# Sonar_Power_Schematic_LT1962.net
KiCad netlist of a schematic drawn in EAGLE
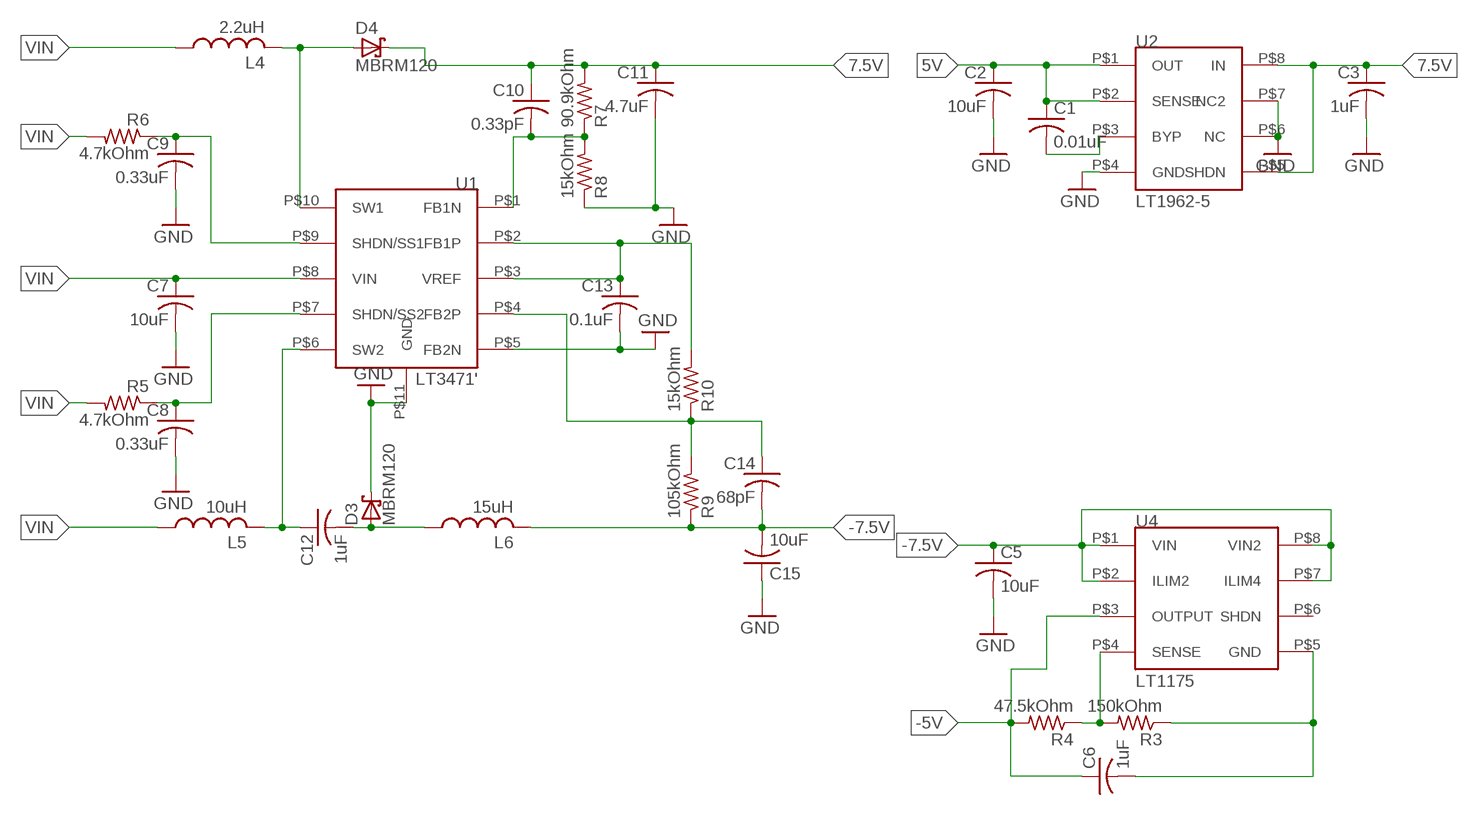
[diagram p0: schematic, sheet 1]

(export (version "E")
  (design (tool "Eeschema 10.0.6"))
  (components
    (comp (ref "C1")
      (value "0.01uF")
      (footprint "eagle-import:C0603")
      (libsource (lib "eagle-import") (part "C-USC0603"))
    )
    (comp (ref "C2")
      (value "10uF")
      (footprint "eagle-import:C0603")
      (libsource (lib "eagle-import") (part "C-USC0603"))
    )
    (comp (ref "C3")
      (value "1uF")
      (footprint "eagle-import:C0603")
      (libsource (lib "eagle-import") (part "C-USC0603"))
    )
    (comp (ref "C5")
      (value "10uF")
      (footprint "eagle-import:C0603")
      (libsource (lib "eagle-import") (part "C-USC0603"))
    )
    (comp (ref "C6")
      (value "1uF")
      (footprint "eagle-import:C0603")
      (libsource (lib "eagle-import") (part "C-USC0603"))
    )
    (comp (ref "C7")
      (value "10uF")
      (footprint "eagle-import:C0603")
      (libsource (lib "eagle-import") (part "C-USC0603"))
    )
    (comp (ref "C8")
      (value "0.33uF")
      (footprint "eagle-import:C0603")
      (libsource (lib "eagle-import") (part "C-USC0603"))
    )
    (comp (ref "C9")
      (value "0.33uF")
      (footprint "eagle-import:C0603")
      (libsource (lib "eagle-import") (part "C-USC0603"))
    )
    (comp (ref "C10")
      (value "0.33pF")
      (footprint "eagle-import:C0603")
      (libsource (lib "eagle-import") (part "C-USC0603"))
    )
    (comp (ref "C11")
      (value "4.7uF")
      (footprint "eagle-import:C0603")
      (libsource (lib "eagle-import") (part "C-USC0603"))
    )
    (comp (ref "C12")
      (value "1uF")
      (footprint "eagle-import:C0603")
      (libsource (lib "eagle-import") (part "C-USC0603"))
    )
    (comp (ref "C13")
      (value "0.1uF")
      (footprint "eagle-import:C0603")
      (libsource (lib "eagle-import") (part "C-USC0603"))
    )
    (comp (ref "C14")
      (value "68pF")
      (footprint "eagle-import:C0603")
      (libsource (lib "eagle-import") (part "C-USC0603"))
    )
    (comp (ref "C15")
      (value "10uF")
      (footprint "eagle-import:C0603")
      (libsource (lib "eagle-import") (part "C-USC0603"))
    )
    (comp (ref "D3")
      (value "MBRM120")
      (footprint "eagle-import:DO-216AA")
      (libsource (lib "eagle-import") (part "MBRM120"))
    )
    (comp (ref "D4")
      (value "MBRM120")
      (footprint "eagle-import:DO-216AA")
      (libsource (lib "eagle-import") (part "MBRM120"))
    )
    (comp (ref "L4")
      (value "2.2uH")
      (footprint "eagle-import:NS4.9X4.9")
      (libsource (lib "eagle-import") (part "LQH5BPN2R2N38L"))
    )
    (comp (ref "L5")
      (value "10uH")
      (footprint "eagle-import:NS5X5")
      (libsource (lib "eagle-import") (part "VLS5045EX-100M2"))
    )
    (comp (ref "L6")
      (value "15uH")
      (footprint "eagle-import:NS5X5")
      (libsource (lib "eagle-import") (part "VLS5045EX-150M-CA1"))
    )
    (comp (ref "R3")
      (value "150kOhm")
      (footprint "eagle-import:R0603")
      (libsource (lib "eagle-import") (part "R-US_R0603"))
    )
    (comp (ref "R4")
      (value "47.5kOhm")
      (footprint "eagle-import:R0603")
      (libsource (lib "eagle-import") (part "R-US_R0603"))
    )
    (comp (ref "R5")
      (value "4.7kOhm")
      (footprint "eagle-import:R0603")
      (libsource (lib "eagle-import") (part "R-US_R0603"))
    )
    (comp (ref "R6")
      (value "4.7kOhm")
      (footprint "eagle-import:R0603")
      (libsource (lib "eagle-import") (part "R-US_R0603"))
    )
    (comp (ref "R7")
      (value "90.9kOhm")
      (footprint "eagle-import:R0603")
      (libsource (lib "eagle-import") (part "R-US_R0603"))
    )
    (comp (ref "R8")
      (value "15kOhm")
      (footprint "eagle-import:R0603")
      (libsource (lib "eagle-import") (part "R-US_R0603"))
    )
    (comp (ref "R9")
      (value "105kOhm")
      (footprint "eagle-import:R0603")
      (libsource (lib "eagle-import") (part "R-US_R0603"))
    )
    (comp (ref "R10")
      (value "15kOhm")
      (footprint "eagle-import:R0603")
      (libsource (lib "eagle-import") (part "R-US_R0603"))
    )
    (comp (ref "U1")
      (value "LT3471'")
      (footprint "eagle-import:10-WFDFN")
      (libsource (lib "eagle-import") (part "LT3471'"))
    )
    (comp (ref "U2")
      (value "LT1962-5")
      (footprint "eagle-import:8-MSOP")
      (libsource (lib "eagle-import") (part "LT1962-5"))
    )
    (comp (ref "U4")
      (value "LT1175")
      (footprint "eagle-import:8-SOIC")
      (libsource (lib "eagle-import") (part "LT1175"))
    )
  )
  (nets
    (net (code "1") (name "-5V") (class "Default")
      (node (ref "C6") (pin "1") (pinfunction "1_1") (pintype "passive"))
      (node (ref "R4") (pin "2") (pinfunction "2_2") (pintype "passive"))
      (node (ref "U4") (pin "P$3") (pinfunction "OUTPUT_P$3") (pintype "bidirectional"))
    )
    (net (code "2") (name "-7.5V") (class "Default")
      (node (ref "C14") (pin "2") (pinfunction "2_2") (pintype "passive"))
      (node (ref "C15") (pin "2") (pinfunction "2_2") (pintype "passive"))
      (node (ref "C5") (pin "1") (pinfunction "1_1") (pintype "passive"))
      (node (ref "L6") (pin "P$2") (pinfunction "2_P$2") (pintype "passive"))
      (node (ref "R9") (pin "1") (pinfunction "1_1") (pintype "passive"))
      (node (ref "U4") (pin "P$1") (pinfunction "VIN_P$1") (pintype "power_in"))
      (node (ref "U4") (pin "P$2") (pinfunction "ILIM2_P$2") (pintype "bidirectional"))
      (node (ref "U4") (pin "P$7") (pinfunction "ILIM4_P$7") (pintype "bidirectional"))
      (node (ref "U4") (pin "P$8") (pinfunction "VIN2_P$8") (pintype "power_in"))
    )
    (net (code "3") (name "5V") (class "Default")
      (node (ref "C1") (pin "1") (pinfunction "1_1") (pintype "passive"))
      (node (ref "C2") (pin "1") (pinfunction "1_1") (pintype "passive"))
      (node (ref "U2") (pin "P$1") (pinfunction "OUT_P$1") (pintype "bidirectional"))
      (node (ref "U2") (pin "P$2") (pinfunction "SENSE_P$2") (pintype "bidirectional"))
    )
    (net (code "4") (name "7.5V") (class "Default")
      (node (ref "C10") (pin "1") (pinfunction "1_1") (pintype "passive"))
      (node (ref "C11") (pin "1") (pinfunction "1_1") (pintype "passive"))
      (node (ref "C3") (pin "1") (pinfunction "1_1") (pintype "passive"))
      (node (ref "D4") (pin "P$1") (pinfunction "C_P$1") (pintype "passive"))
      (node (ref "R7") (pin "2") (pinfunction "2_2") (pintype "passive"))
      (node (ref "U2") (pin "P$5") (pinfunction "SHDN_P$5") (pintype "bidirectional"))
      (node (ref "U2") (pin "P$8") (pinfunction "IN_P$8") (pintype "bidirectional"))
    )
    (net (code "5") (name "GND") (class "Default")
      (node (ref "C11") (pin "2") (pinfunction "2_2") (pintype "passive"))
      (node (ref "C13") (pin "2") (pinfunction "2_2") (pintype "passive"))
      (node (ref "C15") (pin "1") (pinfunction "1_1") (pintype "passive"))
      (node (ref "C2") (pin "2") (pinfunction "2_2") (pintype "passive"))
      (node (ref "C3") (pin "2") (pinfunction "2_2") (pintype "passive"))
      (node (ref "C5") (pin "2") (pinfunction "2_2") (pintype "passive"))
      (node (ref "C7") (pin "2") (pinfunction "2_2") (pintype "passive"))
      (node (ref "C8") (pin "2") (pinfunction "2_2") (pintype "passive"))
      (node (ref "C9") (pin "2") (pinfunction "2_2") (pintype "passive"))
      (node (ref "D3") (pin "P$1") (pinfunction "C_P$1") (pintype "passive"))
      (node (ref "R8") (pin "1") (pinfunction "1_1") (pintype "passive"))
      (node (ref "U1") (pin "P$11") (pinfunction "GND_P$11") (pintype "power_in"))
      (node (ref "U1") (pin "P$5") (pinfunction "FB2N_P$5") (pintype "bidirectional"))
      (node (ref "U2") (pin "P$4") (pinfunction "GND_P$4") (pintype "bidirectional"))
      (node (ref "U2") (pin "P$6") (pinfunction "NC_P$6") (pintype "bidirectional"))
      (node (ref "U2") (pin "P$7") (pinfunction "NC2_P$7") (pintype "bidirectional"))
    )
    (net (code "6") (name "Net-(D3-A)") (class "Default")
      (node (ref "C12") (pin "2") (pinfunction "2_2") (pintype "passive"))
      (node (ref "D3") (pin "P$2") (pinfunction "A_P$2") (pintype "passive"))
      (node (ref "L6") (pin "P$1") (pinfunction "1_P$1") (pintype "passive"))
    )
    (net (code "7") (name "Net-(D4-A)") (class "Default")
      (node (ref "D4") (pin "P$2") (pinfunction "A_P$2") (pintype "passive"))
      (node (ref "L4") (pin "P$2") (pinfunction "2_P$2") (pintype "passive"))
      (node (ref "U1") (pin "P$10") (pinfunction "SW1_P$10") (pintype "bidirectional"))
    )
    (net (code "8") (name "Net-(L5-2)") (class "Default")
      (node (ref "C12") (pin "1") (pinfunction "1_1") (pintype "passive"))
      (node (ref "L5") (pin "P$2") (pinfunction "2_P$2") (pintype "passive"))
      (node (ref "U1") (pin "P$6") (pinfunction "SW2_P$6") (pintype "bidirectional"))
    )
    (net (code "9") (name "Net-(U1-FB1N)") (class "Default")
      (node (ref "C10") (pin "2") (pinfunction "2_2") (pintype "passive"))
      (node (ref "R7") (pin "1") (pinfunction "1_1") (pintype "passive"))
      (node (ref "R8") (pin "2") (pinfunction "2_2") (pintype "passive"))
      (node (ref "U1") (pin "P$1") (pinfunction "FB1N_P$1") (pintype "bidirectional"))
    )
    (net (code "10") (name "Net-(U1-FB1P)") (class "Default")
      (node (ref "C13") (pin "1") (pinfunction "1_1") (pintype "passive"))
      (node (ref "R10") (pin "2") (pinfunction "2_2") (pintype "passive"))
      (node (ref "U1") (pin "P$2") (pinfunction "FB1P_P$2") (pintype "bidirectional"))
      (node (ref "U1") (pin "P$3") (pinfunction "VREF_P$3") (pintype "power_in"))
    )
    (net (code "11") (name "Net-(U1-FB2P)") (class "Default")
      (node (ref "C14") (pin "1") (pinfunction "1_1") (pintype "passive"))
      (node (ref "R10") (pin "1") (pinfunction "1_1") (pintype "passive"))
      (node (ref "R9") (pin "2") (pinfunction "2_2") (pintype "passive"))
      (node (ref "U1") (pin "P$4") (pinfunction "FB2P_P$4") (pintype "bidirectional"))
    )
    (net (code "12") (name "Net-(U1-SHDN{slash}SS1)") (class "Default")
      (node (ref "C9") (pin "1") (pinfunction "1_1") (pintype "passive"))
      (node (ref "R6") (pin "1") (pinfunction "1_1") (pintype "passive"))
      (node (ref "U1") (pin "P$9") (pinfunction "SHDN/SS1_P$9") (pintype "bidirectional"))
    )
    (net (code "13") (name "Net-(U1-SHDN{slash}SS2)") (class "Default")
      (node (ref "C8") (pin "1") (pinfunction "1_1") (pintype "passive"))
      (node (ref "R5") (pin "1") (pinfunction "1_1") (pintype "passive"))
      (node (ref "U1") (pin "P$7") (pinfunction "SHDN/SS2_P$7") (pintype "bidirectional"))
    )
    (net (code "14") (name "Net-(U2-BYP)") (class "Default")
      (node (ref "C1") (pin "2") (pinfunction "2_2") (pintype "passive"))
      (node (ref "U2") (pin "P$3") (pinfunction "BYP_P$3") (pintype "bidirectional"))
    )
    (net (code "15") (name "Net-(U4-GND)") (class "Default")
      (node (ref "C6") (pin "2") (pinfunction "2_2") (pintype "passive"))
      (node (ref "R3") (pin "1") (pinfunction "1_1") (pintype "passive"))
      (node (ref "U4") (pin "P$5") (pinfunction "GND_P$5") (pintype "power_in"))
    )
    (net (code "16") (name "Net-(U4-SENSE)") (class "Default")
      (node (ref "R3") (pin "2") (pinfunction "2_2") (pintype "passive"))
      (node (ref "R4") (pin "1") (pinfunction "1_1") (pintype "passive"))
      (node (ref "U4") (pin "P$4") (pinfunction "SENSE_P$4") (pintype "bidirectional"))
    )
    (net (code "17") (name "VIN") (class "Default")
      (node (ref "C7") (pin "1") (pinfunction "1_1") (pintype "passive"))
      (node (ref "L4") (pin "P$1") (pinfunction "1_P$1") (pintype "passive"))
      (node (ref "L5") (pin "P$1") (pinfunction "1_P$1") (pintype "passive"))
      (node (ref "R5") (pin "2") (pinfunction "2_2") (pintype "passive"))
      (node (ref "R6") (pin "2") (pinfunction "2_2") (pintype "passive"))
      (node (ref "U1") (pin "P$8") (pinfunction "VIN_P$8") (pintype "power_in"))
    )
    (net (code "18") (name "unconnected-(U4-SHDN-PadP$6)") (class "Default")
      (node (ref "U4") (pin "P$6") (pinfunction "SHDN_P$6") (pintype "bidirectional"))
    )
  )
)
